# solenoid_board.net
KiCad netlist of a schematic drawn in EAGLE
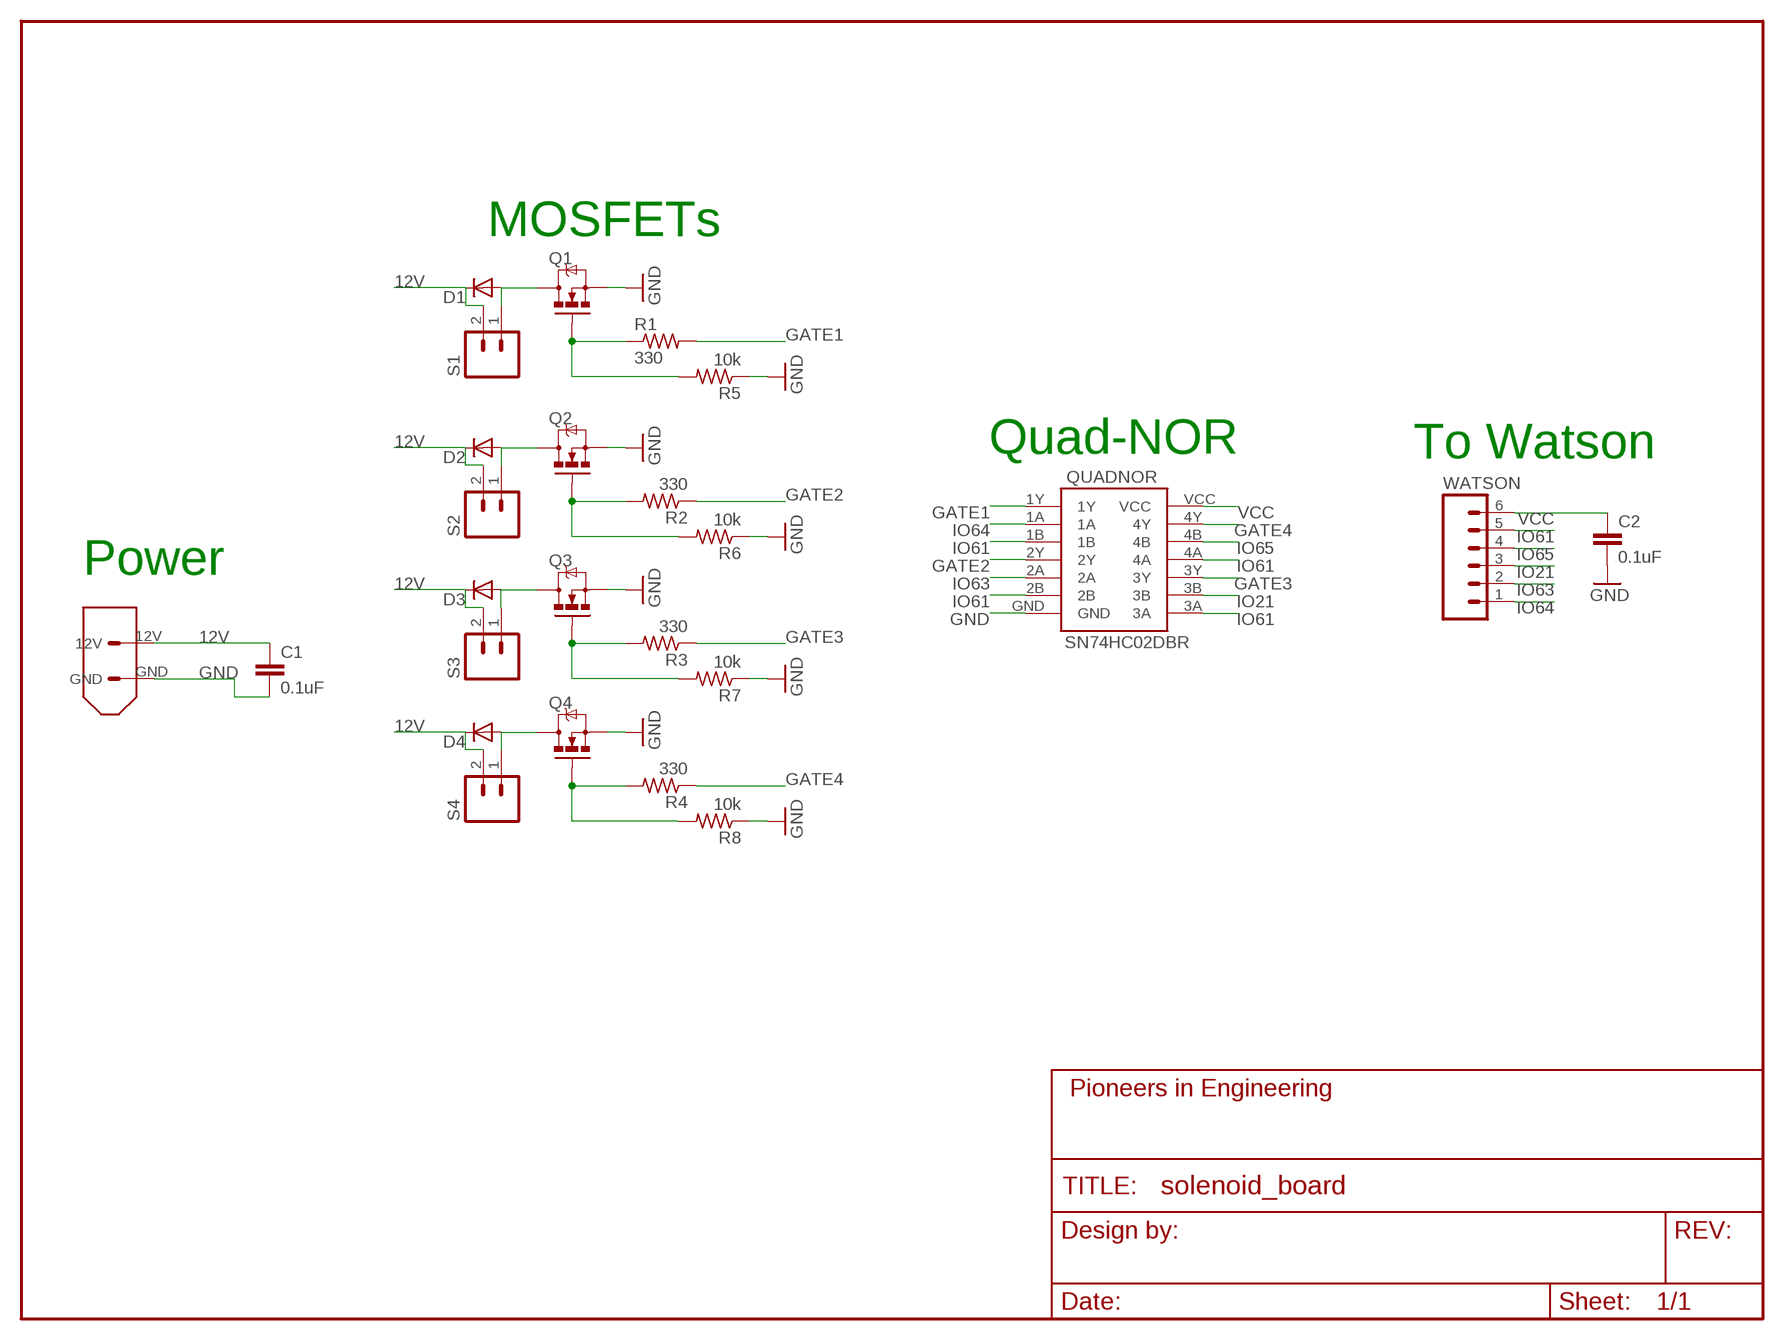
[diagram p0: schematic, sheet 1]

(export (version "E")
  (design (tool "Eeschema 10.0.6"))
  (components
    (comp (ref "C1")
      (value "0.1uF")
      (footprint "eagle-import:0603-CAP")
      (libsource (lib "eagle-import") (part "CAP0603-CAP"))
    )
    (comp (ref "C2")
      (value "0.1uF")
      (footprint "eagle-import:0603-CAP")
      (libsource (lib "eagle-import") (part "CAP0603-CAP"))
    )
    (comp (ref "D1")
      (value "DIODESMA-ALT")
      (footprint "eagle-import:SMA-DIODE_ALT")
      (libsource (lib "eagle-import") (part "DIODESMA-ALT"))
    )
    (comp (ref "D2")
      (value "DIODESMA-ALT")
      (footprint "eagle-import:SMA-DIODE_ALT")
      (libsource (lib "eagle-import") (part "DIODESMA-ALT"))
    )
    (comp (ref "D3")
      (value "DIODESMA-ALT")
      (footprint "eagle-import:SMA-DIODE_ALT")
      (libsource (lib "eagle-import") (part "DIODESMA-ALT"))
    )
    (comp (ref "D4")
      (value "DIODESMA-ALT")
      (footprint "eagle-import:SMA-DIODE_ALT")
      (libsource (lib "eagle-import") (part "DIODESMA-ALT"))
    )
    (comp (ref "Q1")
      (value "MOSFET-NCHANNELSMD")
      (footprint "eagle-import:SOT23-3")
      (libsource (lib "eagle-import") (part "MOSFET-NCHANNELSMD"))
    )
    (comp (ref "Q2")
      (value "MOSFET-NCHANNELSMD")
      (footprint "eagle-import:SOT23-3")
      (libsource (lib "eagle-import") (part "MOSFET-NCHANNELSMD"))
    )
    (comp (ref "Q3")
      (value "MOSFET-NCHANNELSMD")
      (footprint "eagle-import:SOT23-3")
      (libsource (lib "eagle-import") (part "MOSFET-NCHANNELSMD"))
    )
    (comp (ref "Q4")
      (value "MOSFET-NCHANNELSMD")
      (footprint "eagle-import:SOT23-3")
      (libsource (lib "eagle-import") (part "MOSFET-NCHANNELSMD"))
    )
    (comp (ref "QUADNOR")
      (value "SN74HC02DBR")
      (footprint "eagle-import:QUADNOR")
      (fields (field (name "PARTNUMBER") "296-8204-1-ND"))
      (libsource (lib "eagle-import") (part "SN74HC02DBR"))
    )
    (comp (ref "R1")
      (value "330")
      (footprint "eagle-import:R0603")
      (libsource (lib "eagle-import") (part "R-US_R0603"))
    )
    (comp (ref "R2")
      (value "330")
      (footprint "eagle-import:R0603")
      (libsource (lib "eagle-import") (part "R-US_R0603"))
    )
    (comp (ref "R3")
      (value "330")
      (footprint "eagle-import:R0603")
      (libsource (lib "eagle-import") (part "R-US_R0603"))
    )
    (comp (ref "R4")
      (value "330")
      (footprint "eagle-import:R0603")
      (libsource (lib "eagle-import") (part "R-US_R0603"))
    )
    (comp (ref "R5")
      (value "10k")
      (footprint "eagle-import:R0603")
      (libsource (lib "eagle-import") (part "R-US_R0603"))
    )
    (comp (ref "R6")
      (value "10k")
      (footprint "eagle-import:R0603")
      (libsource (lib "eagle-import") (part "R-US_R0603"))
    )
    (comp (ref "R7")
      (value "10k")
      (footprint "eagle-import:R0603")
      (libsource (lib "eagle-import") (part "R-US_R0603"))
    )
    (comp (ref "R8")
      (value "10k")
      (footprint "eagle-import:R0603")
      (libsource (lib "eagle-import") (part "R-US_R0603"))
    )
    (comp (ref "S1")
      (value "M021X02-MTA")
      (footprint "eagle-import:1X02-MTA")
      (fields (field (name "PARTNUMBER") "A1921-ND"))
      (libsource (lib "eagle-import") (part "M021X02-MTA"))
    )
    (comp (ref "S2")
      (value "M021X02-MTA")
      (footprint "eagle-import:1X02-MTA")
      (fields (field (name "PARTNUMBER") "A1921-ND"))
      (libsource (lib "eagle-import") (part "M021X02-MTA"))
    )
    (comp (ref "S3")
      (value "M021X02-MTA")
      (footprint "eagle-import:1X02-MTA")
      (fields (field (name "PARTNUMBER") "A1921-ND"))
      (libsource (lib "eagle-import") (part "M021X02-MTA"))
    )
    (comp (ref "S4")
      (value "M021X02-MTA")
      (footprint "eagle-import:1X02-MTA")
      (fields (field (name "PARTNUMBER") "A1921-ND"))
      (libsource (lib "eagle-import") (part "M021X02-MTA"))
    )
    (comp (ref "U$2")
      (value "XT60CONNECTOR")
      (footprint "eagle-import:XT60CONNECTOR")
      (fields (field (name "PARTNUMBER") "PRT-10474 "))
      (libsource (lib "eagle-import") (part "XT60CONNECTOR"))
    )
    (comp (ref "WATSON")
      (value "M06")
      (footprint "eagle-import:1X06-MTA")
      (fields (field (name "PARTNUMBER") "A1923-ND"))
      (libsource (lib "eagle-import") (part "M06"))
    )
  )
  (nets
    (net (code "1") (name "/12V") (class "Default")
      (node (ref "C1") (pin "1") (pinfunction "1_1") (pintype "passive"))
      (node (ref "D1") (pin "C") (pinfunction "C_C") (pintype "passive"))
      (node (ref "D2") (pin "C") (pinfunction "C_C") (pintype "passive"))
      (node (ref "D3") (pin "C") (pinfunction "C_C") (pintype "passive"))
      (node (ref "D4") (pin "C") (pinfunction "C_C") (pintype "passive"))
      (node (ref "S1") (pin "2") (pinfunction "2_2") (pintype "passive"))
      (node (ref "S2") (pin "2") (pinfunction "2_2") (pintype "passive"))
      (node (ref "S3") (pin "2") (pinfunction "2_2") (pintype "passive"))
      (node (ref "S4") (pin "2") (pinfunction "2_2") (pintype "passive"))
      (node (ref "U$2") (pin "12V") (pinfunction "12V_12V") (pintype "bidirectional"))
    )
    (net (code "2") (name "/GATE1") (class "Default")
      (node (ref "QUADNOR") (pin "1Y") (pinfunction "1Y_1Y") (pintype "bidirectional"))
      (node (ref "R1") (pin "2") (pinfunction "2_2") (pintype "passive"))
    )
    (net (code "3") (name "/GATE2") (class "Default")
      (node (ref "QUADNOR") (pin "2Y") (pinfunction "2Y_2Y") (pintype "bidirectional"))
      (node (ref "R2") (pin "1") (pinfunction "1_1") (pintype "passive"))
    )
    (net (code "4") (name "/GATE3") (class "Default")
      (node (ref "QUADNOR") (pin "3Y") (pinfunction "3Y_3Y") (pintype "bidirectional"))
      (node (ref "R3") (pin "1") (pinfunction "1_1") (pintype "passive"))
    )
    (net (code "5") (name "/GATE4") (class "Default")
      (node (ref "QUADNOR") (pin "4Y") (pinfunction "4Y_4Y") (pintype "bidirectional"))
      (node (ref "R4") (pin "1") (pinfunction "1_1") (pintype "passive"))
    )
    (net (code "6") (name "/IO21") (class "Default")
      (node (ref "QUADNOR") (pin "3B") (pinfunction "3B_3B") (pintype "bidirectional"))
      (node (ref "WATSON") (pin "3") (pinfunction "3_3") (pintype "passive"))
    )
    (net (code "7") (name "/IO61") (class "Default")
      (node (ref "QUADNOR") (pin "1B") (pinfunction "1B_1B") (pintype "bidirectional"))
      (node (ref "QUADNOR") (pin "2B") (pinfunction "2B_2B") (pintype "bidirectional"))
      (node (ref "QUADNOR") (pin "3A") (pinfunction "3A_3A") (pintype "bidirectional"))
      (node (ref "QUADNOR") (pin "4A") (pinfunction "4A_4A") (pintype "bidirectional"))
      (node (ref "WATSON") (pin "5") (pinfunction "5_5") (pintype "passive"))
    )
    (net (code "8") (name "/IO63") (class "Default")
      (node (ref "QUADNOR") (pin "2A") (pinfunction "2A_2A") (pintype "bidirectional"))
      (node (ref "WATSON") (pin "2") (pinfunction "2_2") (pintype "passive"))
    )
    (net (code "9") (name "/IO64") (class "Default")
      (node (ref "QUADNOR") (pin "1A") (pinfunction "1A_1A") (pintype "bidirectional"))
      (node (ref "WATSON") (pin "1") (pinfunction "1_1") (pintype "passive"))
    )
    (net (code "10") (name "/IO65") (class "Default")
      (node (ref "QUADNOR") (pin "4B") (pinfunction "4B_4B") (pintype "bidirectional"))
      (node (ref "WATSON") (pin "4") (pinfunction "4_4") (pintype "passive"))
    )
    (net (code "11") (name "/VCC") (class "Default")
      (node (ref "C2") (pin "1") (pinfunction "1_1") (pintype "passive"))
      (node (ref "QUADNOR") (pin "VCC") (pinfunction "VCC_VCC") (pintype "bidirectional"))
      (node (ref "WATSON") (pin "6") (pinfunction "6_6") (pintype "passive"))
    )
    (net (code "12") (name "GND") (class "Default")
      (node (ref "C1") (pin "2") (pinfunction "2_2") (pintype "passive"))
      (node (ref "C2") (pin "2") (pinfunction "2_2") (pintype "passive"))
      (node (ref "Q1") (pin "2") (pinfunction "S_2") (pintype "passive"))
      (node (ref "Q2") (pin "2") (pinfunction "S_2") (pintype "passive"))
      (node (ref "Q3") (pin "2") (pinfunction "S_2") (pintype "passive"))
      (node (ref "Q4") (pin "2") (pinfunction "S_2") (pintype "passive"))
      (node (ref "QUADNOR") (pin "GND") (pinfunction "GND_GND") (pintype "bidirectional"))
      (node (ref "R5") (pin "1") (pinfunction "1_1") (pintype "passive"))
      (node (ref "R6") (pin "1") (pinfunction "1_1") (pintype "passive"))
      (node (ref "R7") (pin "1") (pinfunction "1_1") (pintype "passive"))
      (node (ref "R8") (pin "1") (pinfunction "1_1") (pintype "passive"))
      (node (ref "U$2") (pin "GND") (pinfunction "GND_GND") (pintype "bidirectional"))
    )
    (net (code "13") (name "Net-(Q1-D)") (class "Default")
      (node (ref "D1") (pin "A") (pinfunction "A_A") (pintype "passive"))
      (node (ref "Q1") (pin "3") (pinfunction "D_3") (pintype "passive"))
      (node (ref "S1") (pin "1") (pinfunction "1_1") (pintype "passive"))
    )
    (net (code "14") (name "Net-(Q1-G)") (class "Default")
      (node (ref "Q1") (pin "1") (pinfunction "G_1") (pintype "passive"))
      (node (ref "R1") (pin "1") (pinfunction "1_1") (pintype "passive"))
      (node (ref "R5") (pin "2") (pinfunction "2_2") (pintype "passive"))
    )
    (net (code "15") (name "Net-(Q2-D)") (class "Default")
      (node (ref "D2") (pin "A") (pinfunction "A_A") (pintype "passive"))
      (node (ref "Q2") (pin "3") (pinfunction "D_3") (pintype "passive"))
      (node (ref "S2") (pin "1") (pinfunction "1_1") (pintype "passive"))
    )
    (net (code "16") (name "Net-(Q2-G)") (class "Default")
      (node (ref "Q2") (pin "1") (pinfunction "G_1") (pintype "passive"))
      (node (ref "R2") (pin "2") (pinfunction "2_2") (pintype "passive"))
      (node (ref "R6") (pin "2") (pinfunction "2_2") (pintype "passive"))
    )
    (net (code "17") (name "Net-(Q3-D)") (class "Default")
      (node (ref "D3") (pin "A") (pinfunction "A_A") (pintype "passive"))
      (node (ref "Q3") (pin "3") (pinfunction "D_3") (pintype "passive"))
      (node (ref "S3") (pin "1") (pinfunction "1_1") (pintype "passive"))
    )
    (net (code "18") (name "Net-(Q3-G)") (class "Default")
      (node (ref "Q3") (pin "1") (pinfunction "G_1") (pintype "passive"))
      (node (ref "R3") (pin "2") (pinfunction "2_2") (pintype "passive"))
      (node (ref "R7") (pin "2") (pinfunction "2_2") (pintype "passive"))
    )
    (net (code "19") (name "Net-(Q4-D)") (class "Default")
      (node (ref "D4") (pin "A") (pinfunction "A_A") (pintype "passive"))
      (node (ref "Q4") (pin "3") (pinfunction "D_3") (pintype "passive"))
      (node (ref "S4") (pin "1") (pinfunction "1_1") (pintype "passive"))
    )
    (net (code "20") (name "Net-(Q4-G)") (class "Default")
      (node (ref "Q4") (pin "1") (pinfunction "G_1") (pintype "passive"))
      (node (ref "R4") (pin "2") (pinfunction "2_2") (pintype "passive"))
      (node (ref "R8") (pin "2") (pinfunction "2_2") (pintype "passive"))
    )
  )
)
